# LCD16x2.net
KiCad netlist of a schematic drawn in Altium Designer
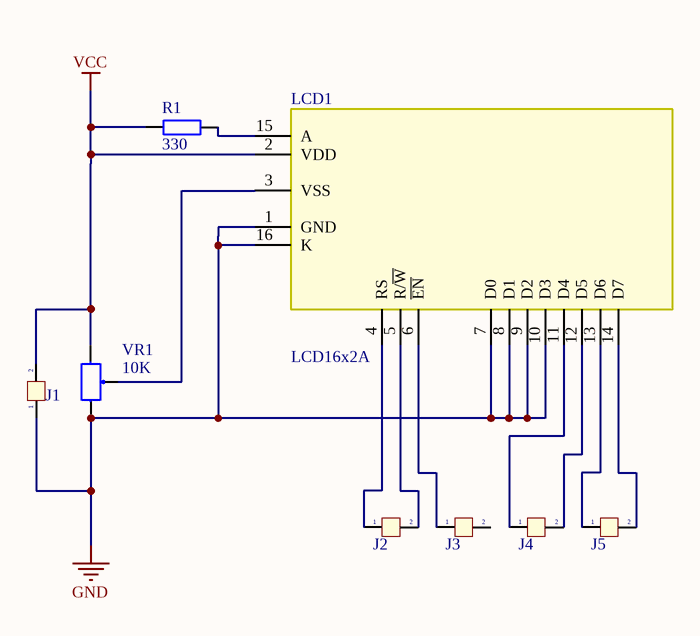
[diagram p0: LCD16x2.SchDoc]

(export (version "E")
  (design (tool "Eeschema 10.0.6"))
  (components
    (comp (ref "J1") (value "Jumper 2") (footprint "JP2") (libsource (lib "Cty1") (part "JP 2")))
    (comp (ref "J2") (value "Jumper 2") (footprint "JP2") (libsource (lib "") (part "JP 2_1")))
    (comp (ref "J3") (value "Jumper 2") (footprint "JP2") (libsource (lib "") (part "JP 2_1")))
    (comp (ref "J4") (value "Jumper 2") (footprint "JP2") (libsource (lib "") (part "JP 2_1")))
    (comp (ref "J5") (value "Jumper 2") (footprint "JP2") (libsource (lib "") (part "JP 2_1")))
    (comp (ref "LCD1")
      (value "LCD16x2A")
      (footprint "LCD16X2")
      (description "LCD dipslay 16 char, 2 line")
      (libsource (lib "syhaunguyen") (part "LCD16x2"))
    )
    (comp (ref "R1")
      (value "330")
      (footprint "R1/4W")
      (description "Resistor 1/4W")
      (libsource (lib "syhaunguyen") (part "R1/4W"))
    )
    (comp (ref "VR1")
      (value "10K")
      (footprint "VR")
      (description "Var Resistor")
      (libsource (lib "syhaunguyen") (part "VR"))
    )
  )
  (nets
    (net (code "1") (name "GND") (class "Default")
      (node (ref "J1") (pin "1") (pinfunction "1_1") (pintype "passive"))
      (node (ref "LCD1") (pin "1") (pinfunction "GND_1") (pintype "passive"))
      (node (ref "LCD1") (pin "10") (pinfunction "D3_10") (pintype "passive"))
      (node (ref "LCD1") (pin "16") (pinfunction "K_16") (pintype "passive"))
      (node (ref "LCD1") (pin "7") (pinfunction "D0_7") (pintype "passive"))
      (node (ref "LCD1") (pin "8") (pinfunction "D1_8") (pintype "passive"))
      (node (ref "LCD1") (pin "9") (pinfunction "D2_9") (pintype "passive"))
      (node (ref "VR1") (pin "3") (pinfunction "3_3") (pintype "passive"))
    )
    (net (code "2") (name "Net-(LCD1-A)") (class "Default")
      (node (ref "LCD1") (pin "15") (pinfunction "A_15") (pintype "passive"))
      (node (ref "R1") (pin "2") (pinfunction "2_2") (pintype "passive"))
    )
    (net (code "3") (name "Net-(LCD1-D4)") (class "Default")
      (node (ref "J4") (pin "1") (pinfunction "1_1") (pintype "passive"))
      (node (ref "LCD1") (pin "11") (pinfunction "D4_11") (pintype "passive"))
    )
    (net (code "4") (name "Net-(LCD1-D5)") (class "Default")
      (node (ref "J4") (pin "2") (pinfunction "2_2") (pintype "passive"))
      (node (ref "LCD1") (pin "12") (pinfunction "D5_12") (pintype "passive"))
    )
    (net (code "5") (name "Net-(LCD1-D6)") (class "Default")
      (node (ref "J5") (pin "1") (pinfunction "1_1") (pintype "passive"))
      (node (ref "LCD1") (pin "13") (pinfunction "D6_13") (pintype "passive"))
    )
    (net (code "6") (name "Net-(LCD1-D7)") (class "Default")
      (node (ref "J5") (pin "2") (pinfunction "2_2") (pintype "passive"))
      (node (ref "LCD1") (pin "14") (pinfunction "D7_14") (pintype "passive"))
    )
    (net (code "7") (name "Net-(LCD1-RS)") (class "Default")
      (node (ref "J2") (pin "1") (pinfunction "1_1") (pintype "passive"))
      (node (ref "LCD1") (pin "4") (pinfunction "RS_4") (pintype "passive"))
    )
    (net (code "8") (name "Net-(LCD1-R{slash}~{W})") (class "Default")
      (node (ref "J2") (pin "2") (pinfunction "2_2") (pintype "passive"))
      (node (ref "LCD1") (pin "5") (pinfunction "R/~{W}_5") (pintype "passive"))
    )
    (net (code "9") (name "Net-(LCD1-VSS)") (class "Default")
      (node (ref "LCD1") (pin "3") (pinfunction "VSS_3") (pintype "passive"))
      (node (ref "VR1") (pin "2") (pinfunction "2_2") (pintype "passive"))
    )
    (net (code "10") (name "Net-(LCD1-~{EN})") (class "Default")
      (node (ref "J3") (pin "1") (pinfunction "1_1") (pintype "passive"))
      (node (ref "LCD1") (pin "6") (pinfunction "~{EN}_6") (pintype "passive"))
    )
    (net (code "11") (name "VCC") (class "Default")
      (node (ref "J1") (pin "2") (pinfunction "2_2") (pintype "passive"))
      (node (ref "LCD1") (pin "2") (pinfunction "VDD_2") (pintype "passive"))
      (node (ref "R1") (pin "1") (pinfunction "1_1") (pintype "passive"))
      (node (ref "VR1") (pin "1") (pinfunction "1_1") (pintype "passive"))
    )
    (net (code "12") (name "unconnected-(J3-Pad2)") (class "Default")
      (node (ref "J3") (pin "2") (pinfunction "2_2") (pintype "passive"))
    )
  )
)
